# 01.net
KiCad netlist of a schematic drawn in EAGLE
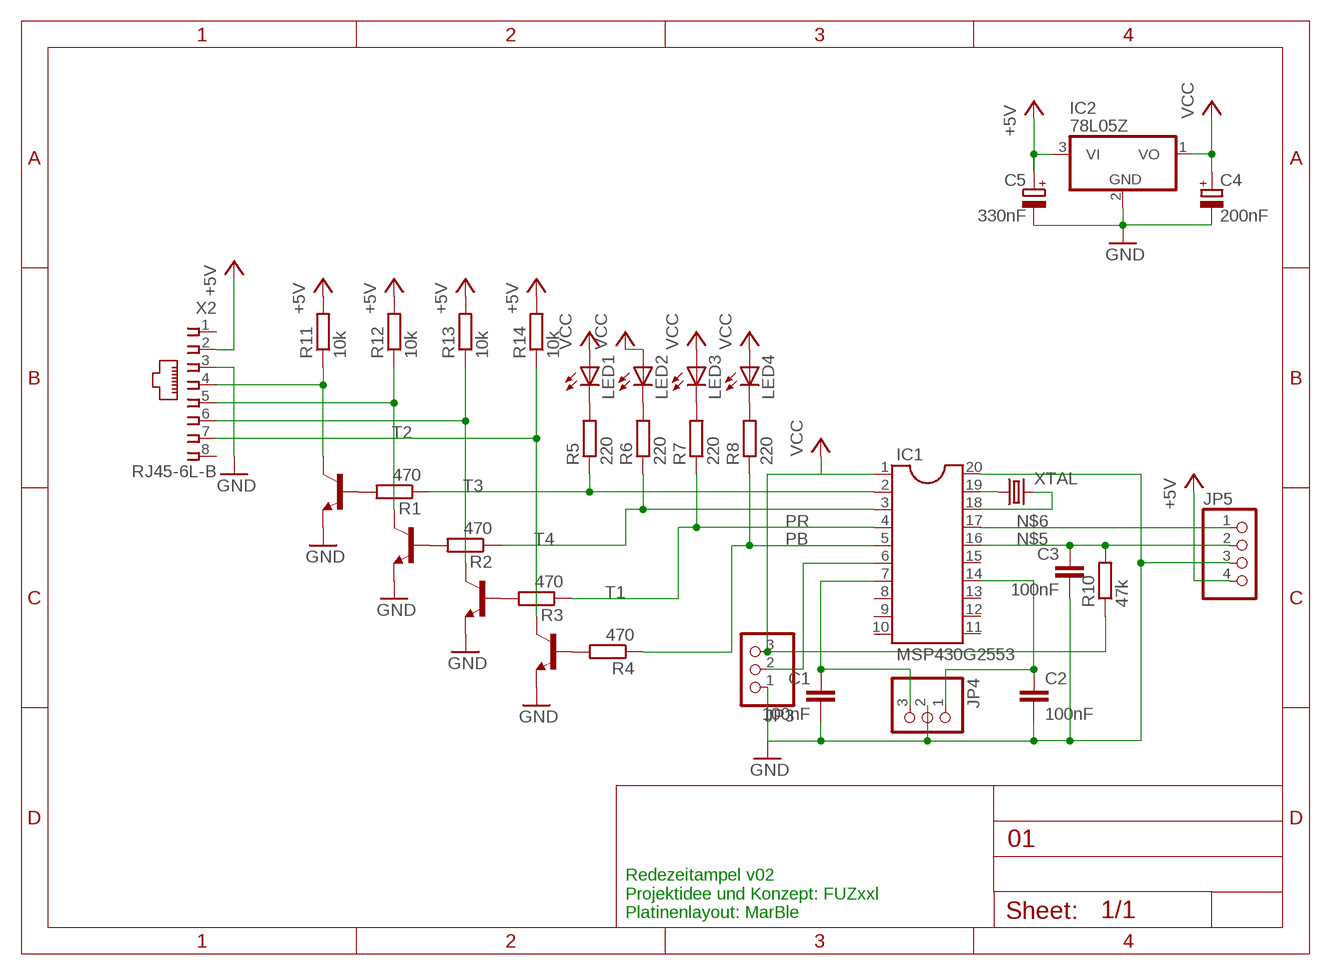
[diagram p0: schematic, sheet 1]

(export (version "E")
  (design (tool "Eeschema 10.0.6"))
  (components
    (comp (ref "C1")
      (value "100nF")
      (footprint "eagle-import:C025-024X044")
      (libsource (lib "eagle-import") (part "C-EU025-024X044"))
    )
    (comp (ref "C2")
      (value "100nF")
      (footprint "eagle-import:C025-024X044")
      (libsource (lib "eagle-import") (part "C-EU025-024X044"))
    )
    (comp (ref "C3")
      (value "100nF")
      (footprint "eagle-import:C025-024X044")
      (libsource (lib "eagle-import") (part "C-EU025-024X044"))
    )
    (comp (ref "C4")
      (value "200nF")
      (footprint "eagle-import:B45181A")
      (libsource (lib "eagle-import") (part "CPOL-EUB45181A"))
    )
    (comp (ref "C5")
      (value "330nF")
      (footprint "eagle-import:B45181A")
      (libsource (lib "eagle-import") (part "CPOL-EUB45181A"))
    )
    (comp (ref "IC1")
      (value "MSP430G2553")
      (footprint "eagle-import:DIL20")
      (libsource (lib "eagle-import") (part "DIL20"))
    )
    (comp (ref "IC2")
      (value "78L05Z")
      (footprint "eagle-import:TO92")
      (libsource (lib "eagle-import") (part "78ZL05"))
    )
    (comp (ref "JP3")
      (value "PINHD-1X3")
      (footprint "eagle-import:1X03")
      (libsource (lib "eagle-import") (part "PINHD-1X3"))
    )
    (comp (ref "JP4")
      (value "PINHD-1X3")
      (footprint "eagle-import:1X03")
      (libsource (lib "eagle-import") (part "PINHD-1X3"))
    )
    (comp (ref "JP5")
      (value "PINHD-1X4/90")
      (footprint "eagle-import:1X04_90")
      (libsource (lib "eagle-import") (part "PINHD-1X4/90"))
    )
    (comp (ref "LED1")
      (value "LED5MM")
      (footprint "eagle-import:LED5MM")
      (libsource (lib "eagle-import") (part "LED5MM"))
    )
    (comp (ref "LED2")
      (value "LED5MM")
      (footprint "eagle-import:LED5MM")
      (libsource (lib "eagle-import") (part "LED5MM"))
    )
    (comp (ref "LED3")
      (value "LED5MM")
      (footprint "eagle-import:LED5MM")
      (libsource (lib "eagle-import") (part "LED5MM"))
    )
    (comp (ref "LED4")
      (value "LED5MM")
      (footprint "eagle-import:LED5MM")
      (libsource (lib "eagle-import") (part "LED5MM"))
    )
    (comp (ref "R1")
      (value "470")
      (footprint "eagle-import:0207_10")
      (libsource (lib "eagle-import") (part "R-EU_0207/10"))
    )
    (comp (ref "R2")
      (value "470")
      (footprint "eagle-import:0207_10")
      (libsource (lib "eagle-import") (part "R-EU_0207/10"))
    )
    (comp (ref "R3")
      (value "470")
      (footprint "eagle-import:0207_10")
      (libsource (lib "eagle-import") (part "R-EU_0207/10"))
    )
    (comp (ref "R4")
      (value "470")
      (footprint "eagle-import:0207_10")
      (libsource (lib "eagle-import") (part "R-EU_0207/10"))
    )
    (comp (ref "R5")
      (value "220")
      (footprint "eagle-import:0207_10")
      (libsource (lib "eagle-import") (part "R-EU_0207/10"))
    )
    (comp (ref "R6")
      (value "220")
      (footprint "eagle-import:0207_10")
      (libsource (lib "eagle-import") (part "R-EU_0207/10"))
    )
    (comp (ref "R7")
      (value "220")
      (footprint "eagle-import:0207_10")
      (libsource (lib "eagle-import") (part "R-EU_0207/10"))
    )
    (comp (ref "R8")
      (value "220")
      (footprint "eagle-import:0207_10")
      (libsource (lib "eagle-import") (part "R-EU_0207/10"))
    )
    (comp (ref "R10")
      (value "47k")
      (footprint "eagle-import:0207_10")
      (libsource (lib "eagle-import") (part "R-EU_0207/10"))
    )
    (comp (ref "R11")
      (value "10k")
      (footprint "eagle-import:0207_10")
      (libsource (lib "eagle-import") (part "R-EU_0207/10"))
    )
    (comp (ref "R12")
      (value "10k")
      (footprint "eagle-import:0207_10")
      (libsource (lib "eagle-import") (part "R-EU_0207/10"))
    )
    (comp (ref "R13")
      (value "10k")
      (footprint "eagle-import:0207_10")
      (libsource (lib "eagle-import") (part "R-EU_0207/10"))
    )
    (comp (ref "R14")
      (value "10k")
      (footprint "eagle-import:0207_10")
      (libsource (lib "eagle-import") (part "R-EU_0207/10"))
    )
    (comp (ref "T1")
      (value "-NPN-TO92-EBC")
      (footprint "eagle-import:TO92-EBC")
      (libsource (lib "eagle-import") (part "-NPN-TO92-EBC"))
    )
    (comp (ref "T2")
      (value "-NPN-TO92-EBC")
      (footprint "eagle-import:TO92-EBC")
      (libsource (lib "eagle-import") (part "-NPN-TO92-EBC"))
    )
    (comp (ref "T3")
      (value "-NPN-TO92-EBC")
      (footprint "eagle-import:TO92-EBC")
      (libsource (lib "eagle-import") (part "-NPN-TO92-EBC"))
    )
    (comp (ref "T4")
      (value "-NPN-TO92-EBC")
      (footprint "eagle-import:TO92-EBC")
      (libsource (lib "eagle-import") (part "-NPN-TO92-EBC"))
    )
    (comp (ref "X2")
      (value "RJ45-6L-B")
      (footprint "eagle-import:RJ45-NO-SHIELD")
      (libsource (lib "eagle-import") (part "RJ45-6L-B"))
    )
    (comp (ref "XTAL")
      (value "CRYSTALTC26H")
      (footprint "eagle-import:TC26H")
      (libsource (lib "eagle-import") (part "CRYSTALTC26H"))
    )
  )
  (nets
    (net (code "1") (name "+5V") (class "Default")
      (node (ref "C5") (pin "+") (pinfunction "+_+") (pintype "passive"))
      (node (ref "IC2") (pin "3") (pinfunction "VI_3") (pintype "input"))
      (node (ref "JP5") (pin "4") (pinfunction "4_4") (pintype "passive"))
      (node (ref "R11") (pin "2") (pinfunction "2_2") (pintype "passive"))
      (node (ref "R12") (pin "2") (pinfunction "2_2") (pintype "passive"))
      (node (ref "R13") (pin "2") (pinfunction "2_2") (pintype "passive"))
      (node (ref "R14") (pin "2") (pinfunction "2_2") (pintype "passive"))
      (node (ref "X2") (pin "2") (pinfunction "2_2") (pintype "passive"))
    )
    (net (code "2") (name "/N$5") (class "Default")
      (node (ref "C3") (pin "1") (pinfunction "1_1") (pintype "passive"))
      (node (ref "IC1") (pin "16") (pinfunction "16_16") (pintype "passive"))
      (node (ref "JP5") (pin "2") (pinfunction "2_2") (pintype "passive"))
      (node (ref "R10") (pin "2") (pinfunction "2_2") (pintype "passive"))
    )
    (net (code "3") (name "/N$6") (class "Default")
      (node (ref "IC1") (pin "17") (pinfunction "17_17") (pintype "passive"))
      (node (ref "JP5") (pin "1") (pinfunction "1_1") (pintype "passive"))
    )
    (net (code "4") (name "/PB") (class "Default")
      (node (ref "IC1") (pin "5") (pinfunction "5_5") (pintype "passive"))
      (node (ref "R4") (pin "1") (pinfunction "1_1") (pintype "passive"))
      (node (ref "R8") (pin "1") (pinfunction "1_1") (pintype "passive"))
    )
    (net (code "5") (name "/PR") (class "Default")
      (node (ref "IC1") (pin "4") (pinfunction "4_4") (pintype "passive"))
      (node (ref "R3") (pin "1") (pinfunction "1_1") (pintype "passive"))
      (node (ref "R7") (pin "1") (pinfunction "1_1") (pintype "passive"))
    )
    (net (code "6") (name "GND") (class "Default")
      (node (ref "C1") (pin "2") (pinfunction "2_2") (pintype "passive"))
      (node (ref "C2") (pin "2") (pinfunction "2_2") (pintype "passive"))
      (node (ref "C3") (pin "2") (pinfunction "2_2") (pintype "passive"))
      (node (ref "C4") (pin "-") (pinfunction "-_-") (pintype "passive"))
      (node (ref "C5") (pin "-") (pinfunction "-_-") (pintype "passive"))
      (node (ref "IC1") (pin "20") (pinfunction "20_20") (pintype "passive"))
      (node (ref "IC2") (pin "2") (pinfunction "GND_2") (pintype "passive"))
      (node (ref "JP3") (pin "1") (pinfunction "1_1") (pintype "passive"))
      (node (ref "JP4") (pin "2") (pinfunction "2_2") (pintype "passive"))
      (node (ref "JP5") (pin "3") (pinfunction "3_3") (pintype "passive"))
      (node (ref "T1") (pin "E") (pinfunction "E_E") (pintype "passive"))
      (node (ref "T2") (pin "E") (pinfunction "E_E") (pintype "passive"))
      (node (ref "T3") (pin "E") (pinfunction "E_E") (pintype "passive"))
      (node (ref "T4") (pin "E") (pinfunction "E_E") (pintype "passive"))
      (node (ref "X2") (pin "3") (pinfunction "3_3") (pintype "passive"))
    )
    (net (code "7") (name "Net-(C1-Pad1)") (class "Default")
      (node (ref "C1") (pin "1") (pinfunction "1_1") (pintype "passive"))
      (node (ref "IC1") (pin "7") (pinfunction "7_7") (pintype "passive"))
      (node (ref "JP4") (pin "3") (pinfunction "3_3") (pintype "passive"))
    )
    (net (code "8") (name "Net-(C2-Pad1)") (class "Default")
      (node (ref "C2") (pin "1") (pinfunction "1_1") (pintype "passive"))
      (node (ref "IC1") (pin "14") (pinfunction "14_14") (pintype "passive"))
      (node (ref "JP4") (pin "1") (pinfunction "1_1") (pintype "passive"))
    )
    (net (code "9") (name "Net-(IC1-Pad2)") (class "Default")
      (node (ref "IC1") (pin "2") (pinfunction "2_2") (pintype "passive"))
      (node (ref "R1") (pin "1") (pinfunction "1_1") (pintype "passive"))
      (node (ref "R5") (pin "1") (pinfunction "1_1") (pintype "passive"))
    )
    (net (code "10") (name "Net-(IC1-Pad3)") (class "Default")
      (node (ref "IC1") (pin "3") (pinfunction "3_3") (pintype "passive"))
      (node (ref "R2") (pin "1") (pinfunction "1_1") (pintype "passive"))
      (node (ref "R6") (pin "1") (pinfunction "1_1") (pintype "passive"))
    )
    (net (code "11") (name "Net-(IC1-Pad6)") (class "Default")
      (node (ref "IC1") (pin "6") (pinfunction "6_6") (pintype "passive"))
      (node (ref "JP3") (pin "2") (pinfunction "2_2") (pintype "passive"))
    )
    (net (code "12") (name "Net-(IC1-Pad18)") (class "Default")
      (node (ref "IC1") (pin "18") (pinfunction "18_18") (pintype "passive"))
      (node (ref "XTAL") (pin "2") (pinfunction "2_2") (pintype "passive"))
    )
    (net (code "13") (name "Net-(IC1-Pad19)") (class "Default")
      (node (ref "IC1") (pin "19") (pinfunction "19_19") (pintype "passive"))
      (node (ref "XTAL") (pin "1") (pinfunction "1_1") (pintype "passive"))
    )
    (net (code "14") (name "Net-(LED1-C)") (class "Default")
      (node (ref "LED1") (pin "K") (pinfunction "C_K") (pintype "passive"))
      (node (ref "R5") (pin "2") (pinfunction "2_2") (pintype "passive"))
    )
    (net (code "15") (name "Net-(LED2-C)") (class "Default")
      (node (ref "LED2") (pin "K") (pinfunction "C_K") (pintype "passive"))
      (node (ref "R6") (pin "2") (pinfunction "2_2") (pintype "passive"))
    )
    (net (code "16") (name "Net-(LED3-C)") (class "Default")
      (node (ref "LED3") (pin "K") (pinfunction "C_K") (pintype "passive"))
      (node (ref "R7") (pin "2") (pinfunction "2_2") (pintype "passive"))
    )
    (net (code "17") (name "Net-(LED4-C)") (class "Default")
      (node (ref "LED4") (pin "K") (pinfunction "C_K") (pintype "passive"))
      (node (ref "R8") (pin "2") (pinfunction "2_2") (pintype "passive"))
    )
    (net (code "18") (name "Net-(R1-Pad2)") (class "Default")
      (node (ref "R1") (pin "2") (pinfunction "2_2") (pintype "passive"))
      (node (ref "T2") (pin "B") (pinfunction "B_B") (pintype "passive"))
    )
    (net (code "19") (name "Net-(R2-Pad2)") (class "Default")
      (node (ref "R2") (pin "2") (pinfunction "2_2") (pintype "passive"))
      (node (ref "T3") (pin "B") (pinfunction "B_B") (pintype "passive"))
    )
    (net (code "20") (name "Net-(R3-Pad2)") (class "Default")
      (node (ref "R3") (pin "2") (pinfunction "2_2") (pintype "passive"))
      (node (ref "T4") (pin "B") (pinfunction "B_B") (pintype "passive"))
    )
    (net (code "21") (name "Net-(R4-Pad2)") (class "Default")
      (node (ref "R4") (pin "2") (pinfunction "2_2") (pintype "passive"))
      (node (ref "T1") (pin "B") (pinfunction "B_B") (pintype "passive"))
    )
    (net (code "22") (name "Net-(R11-Pad1)") (class "Default")
      (node (ref "R11") (pin "1") (pinfunction "1_1") (pintype "passive"))
      (node (ref "T2") (pin "C") (pinfunction "C_C") (pintype "passive"))
      (node (ref "X2") (pin "4") (pinfunction "4_4") (pintype "passive"))
    )
    (net (code "23") (name "Net-(R12-Pad1)") (class "Default")
      (node (ref "R12") (pin "1") (pinfunction "1_1") (pintype "passive"))
      (node (ref "T3") (pin "C") (pinfunction "C_C") (pintype "passive"))
      (node (ref "X2") (pin "5") (pinfunction "5_5") (pintype "passive"))
    )
    (net (code "24") (name "Net-(R13-Pad1)") (class "Default")
      (node (ref "R13") (pin "1") (pinfunction "1_1") (pintype "passive"))
      (node (ref "T4") (pin "C") (pinfunction "C_C") (pintype "passive"))
      (node (ref "X2") (pin "6") (pinfunction "6_6") (pintype "passive"))
    )
    (net (code "25") (name "Net-(R14-Pad1)") (class "Default")
      (node (ref "R14") (pin "1") (pinfunction "1_1") (pintype "passive"))
      (node (ref "T1") (pin "C") (pinfunction "C_C") (pintype "passive"))
      (node (ref "X2") (pin "7") (pinfunction "7_7") (pintype "passive"))
    )
    (net (code "26") (name "VCC") (class "Default")
      (node (ref "C4") (pin "+") (pinfunction "+_+") (pintype "passive"))
      (node (ref "IC1") (pin "1") (pinfunction "1_1") (pintype "passive"))
      (node (ref "IC2") (pin "1") (pinfunction "VO_1") (pintype "passive"))
      (node (ref "JP3") (pin "3") (pinfunction "3_3") (pintype "passive"))
      (node (ref "LED1") (pin "A") (pinfunction "A_A") (pintype "passive"))
      (node (ref "LED2") (pin "A") (pinfunction "A_A") (pintype "passive"))
      (node (ref "LED3") (pin "A") (pinfunction "A_A") (pintype "passive"))
      (node (ref "LED4") (pin "A") (pinfunction "A_A") (pintype "passive"))
      (node (ref "R10") (pin "1") (pinfunction "1_1") (pintype "passive"))
    )
    (net (code "27") (name "unconnected-(IC1-Pad8)") (class "Default")
      (node (ref "IC1") (pin "8") (pinfunction "8_8") (pintype "passive"))
    )
    (net (code "28") (name "unconnected-(IC1-Pad9)") (class "Default")
      (node (ref "IC1") (pin "9") (pinfunction "9_9") (pintype "passive"))
    )
    (net (code "29") (name "unconnected-(IC1-Pad10)") (class "Default")
      (node (ref "IC1") (pin "10") (pinfunction "10_10") (pintype "passive"))
    )
    (net (code "30") (name "unconnected-(IC1-Pad11)") (class "Default")
      (node (ref "IC1") (pin "11") (pinfunction "11_11") (pintype "passive"))
    )
    (net (code "31") (name "unconnected-(IC1-Pad12)") (class "Default")
      (node (ref "IC1") (pin "12") (pinfunction "12_12") (pintype "passive"))
    )
    (net (code "32") (name "unconnected-(IC1-Pad13)") (class "Default")
      (node (ref "IC1") (pin "13") (pinfunction "13_13") (pintype "passive"))
    )
    (net (code "33") (name "unconnected-(IC1-Pad15)") (class "Default")
      (node (ref "IC1") (pin "15") (pinfunction "15_15") (pintype "passive"))
    )
    (net (code "34") (name "unconnected-(X2-Pad1)") (class "Default")
      (node (ref "X2") (pin "1") (pinfunction "1_1") (pintype "passive"))
    )
    (net (code "35") (name "unconnected-(X2-Pad8)") (class "Default")
      (node (ref "X2") (pin "8") (pinfunction "8_8") (pintype "passive"))
    )
  )
)
